# DASH_BOARD.net
KiCad netlist of a schematic drawn in EAGLE
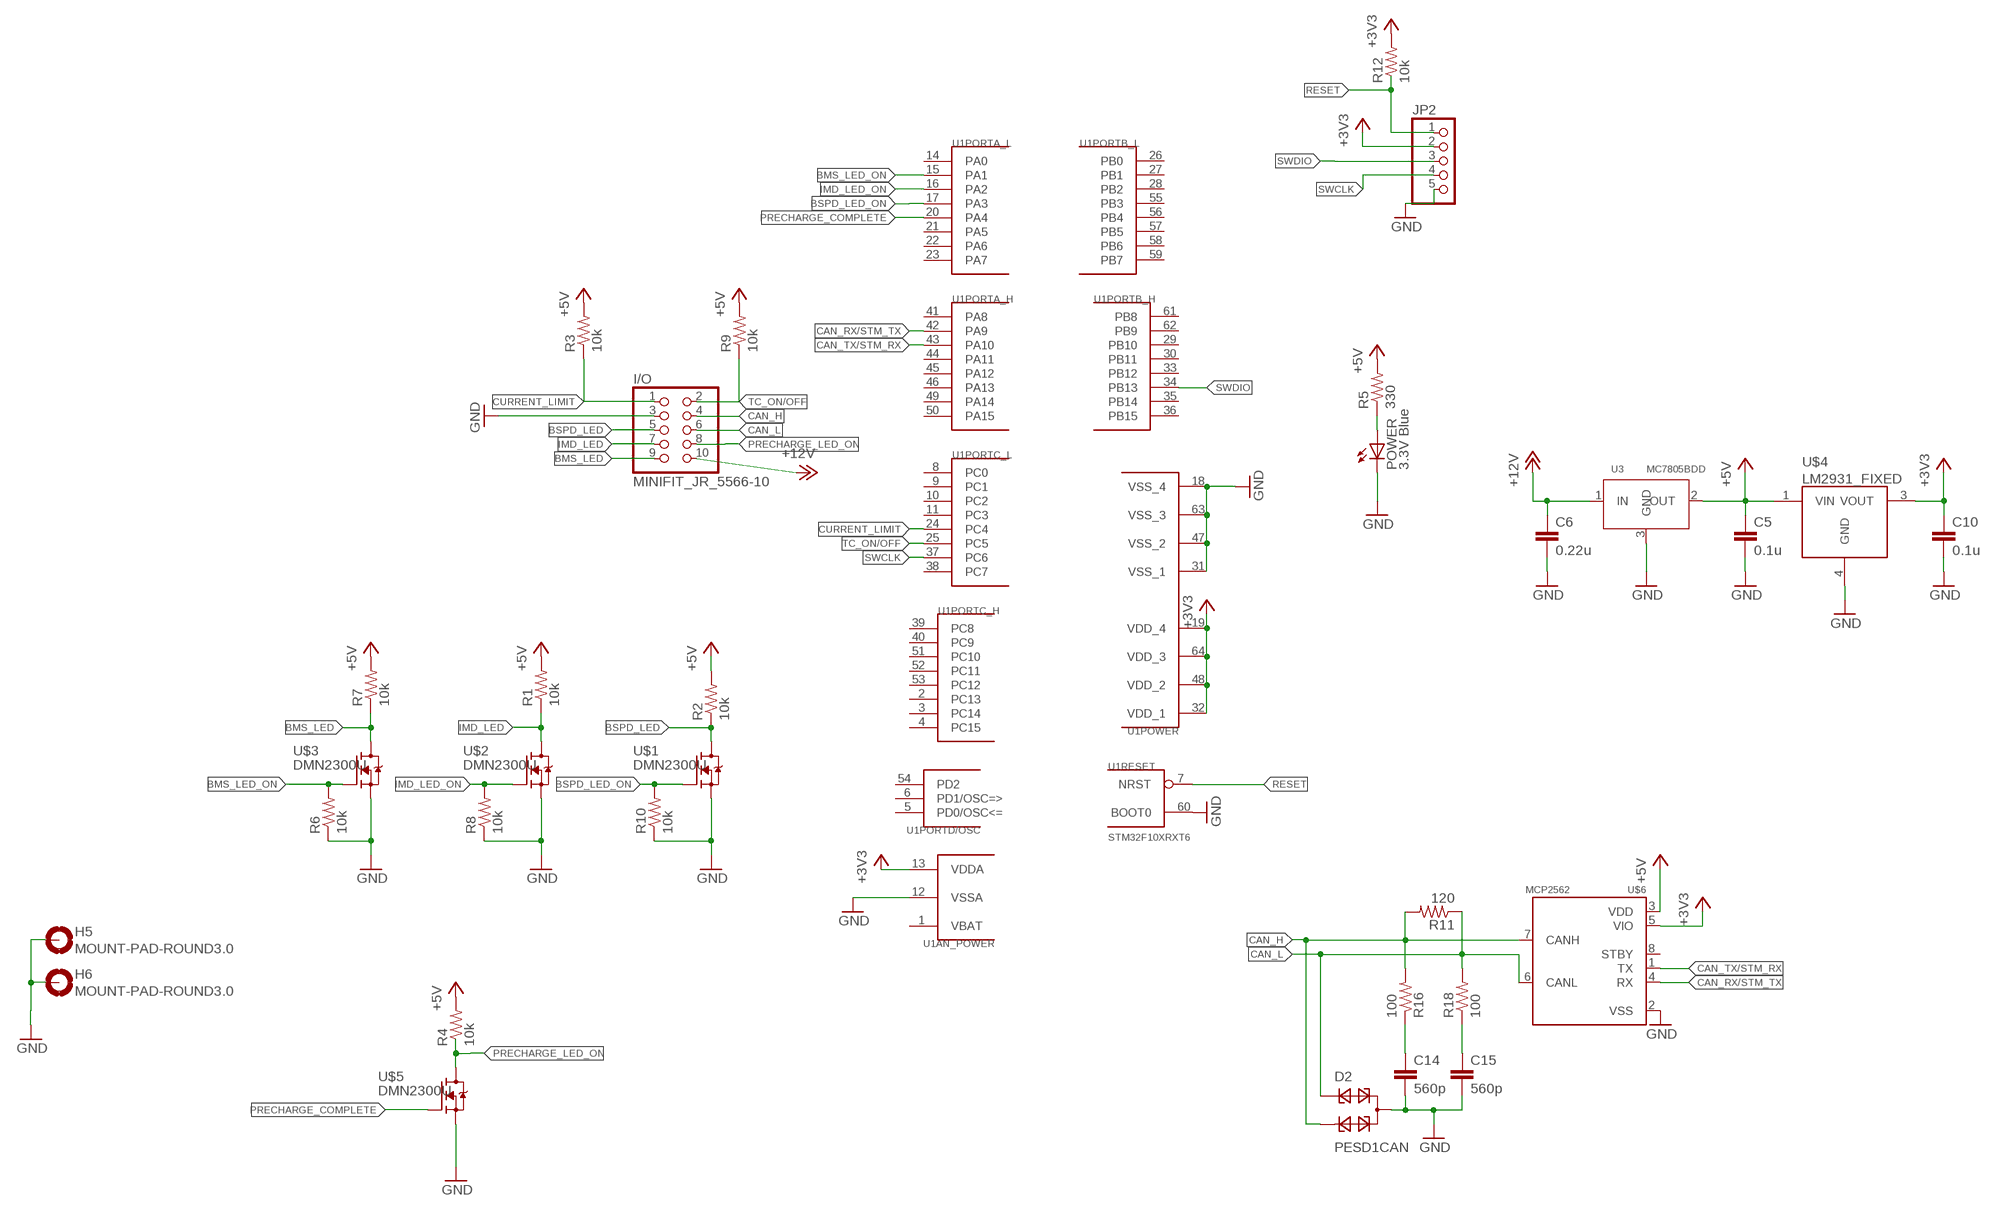
[diagram p0: schematic, sheet 1]

(export (version "E")
  (design (tool "Eeschema 10.0.6"))
  (components
    (comp (ref "C5")
      (value "0.1u")
      (footprint "eagle-import:C0805K")
      (libsource (lib "eagle-import") (part "C-EUC0805K"))
    )
    (comp (ref "C6")
      (value "0.22u")
      (footprint "eagle-import:C0805K")
      (libsource (lib "eagle-import") (part "C-EUC0805K"))
    )
    (comp (ref "C10")
      (value "0.1u")
      (footprint "eagle-import:C0805K")
      (libsource (lib "eagle-import") (part "C-EUC0805K"))
    )
    (comp (ref "C14")
      (value "560p")
      (footprint "eagle-import:C0805K")
      (libsource (lib "eagle-import") (part "C-EUC0805K"))
    )
    (comp (ref "C15")
      (value "560p")
      (footprint "eagle-import:C0805K")
      (libsource (lib "eagle-import") (part "C-EUC0805K"))
    )
    (comp (ref "D2")
      (value "PESD1CAN")
      (footprint "eagle-import:SOT23")
      (libsource (lib "eagle-import") (part "PESD1CAN"))
    )
    (comp (ref "H5")
      (value "MOUNT-PAD-ROUND3.0")
      (footprint "eagle-import:3,0-PAD")
      (libsource (lib "eagle-import") (part "MOUNT-PAD-ROUND3.0"))
    )
    (comp (ref "H6")
      (value "MOUNT-PAD-ROUND3.0")
      (footprint "eagle-import:3,0-PAD")
      (libsource (lib "eagle-import") (part "MOUNT-PAD-ROUND3.0"))
    )
    (comp (ref "I/O")
      (value "MINIFIT_JR_5566-10")
      (footprint "eagle-import:MINIFIT_JR_5566-10")
      (libsource (lib "eagle-import") (part "MINIFIT_JR_5566-10"))
    )
    (comp (ref "JP2")
      (value "PINHD-1X5")
      (footprint "eagle-import:1X05")
      (libsource (lib "eagle-import") (part "PINHD-1X5"))
    )
    (comp (ref "POWER")
      (value "3.3V Blue")
      (footprint "eagle-import:SML0805")
      (libsource (lib "eagle-import") (part "LEDSML0805"))
    )
    (comp (ref "R1")
      (value "10k")
      (footprint "eagle-import:R0805")
      (libsource (lib "eagle-import") (part "resistor_348_R-US_R0805"))
    )
    (comp (ref "R2")
      (value "10k")
      (footprint "eagle-import:R0805")
      (libsource (lib "eagle-import") (part "resistor_348_R-US_R0805"))
    )
    (comp (ref "R3")
      (value "10k")
      (footprint "eagle-import:R0805")
      (libsource (lib "eagle-import") (part "resistor_348_R-US_R0805"))
    )
    (comp (ref "R4")
      (value "10k")
      (footprint "eagle-import:R0805")
      (libsource (lib "eagle-import") (part "resistor_348_R-US_R0805"))
    )
    (comp (ref "R5")
      (value "330")
      (footprint "eagle-import:R0805")
      (libsource (lib "eagle-import") (part "R-US_R0805"))
    )
    (comp (ref "R6")
      (value "10k")
      (footprint "eagle-import:R0805")
      (libsource (lib "eagle-import") (part "resistor_348_R-US_R0805"))
    )
    (comp (ref "R7")
      (value "10k")
      (footprint "eagle-import:R0805")
      (libsource (lib "eagle-import") (part "resistor_348_R-US_R0805"))
    )
    (comp (ref "R8")
      (value "10k")
      (footprint "eagle-import:R0805")
      (libsource (lib "eagle-import") (part "resistor_348_R-US_R0805"))
    )
    (comp (ref "R9")
      (value "10k")
      (footprint "eagle-import:R0805")
      (libsource (lib "eagle-import") (part "resistor_348_R-US_R0805"))
    )
    (comp (ref "R10")
      (value "10k")
      (footprint "eagle-import:R0805")
      (libsource (lib "eagle-import") (part "resistor_348_R-US_R0805"))
    )
    (comp (ref "R11")
      (value "120")
      (footprint "eagle-import:R0805")
      (libsource (lib "eagle-import") (part "R-US_R0805"))
    )
    (comp (ref "R12")
      (value "10k")
      (footprint "eagle-import:R0805")
      (libsource (lib "eagle-import") (part "resistor_348_R-US_R0805"))
    )
    (comp (ref "R16")
      (value "100")
      (footprint "eagle-import:R0805")
      (libsource (lib "eagle-import") (part "R-US_R0805"))
    )
    (comp (ref "R18")
      (value "100")
      (footprint "eagle-import:R0805")
      (libsource (lib "eagle-import") (part "R-US_R0805"))
    )
    (comp (ref "U$1")
      (value "DMN2300U")
      (footprint "eagle-import:SOT23")
      (libsource (lib "eagle-import") (part "DMN2300U"))
    )
    (comp (ref "U$2")
      (value "DMN2300U")
      (footprint "eagle-import:SOT23")
      (libsource (lib "eagle-import") (part "DMN2300U"))
    )
    (comp (ref "U$3")
      (value "DMN2300U")
      (footprint "eagle-import:SOT23")
      (libsource (lib "eagle-import") (part "DMN2300U"))
    )
    (comp (ref "U$4")
      (value "LM2931_FIXED")
      (footprint "eagle-import:DPAK")
      (libsource (lib "eagle-import") (part "LM2931_FIXED"))
    )
    (comp (ref "U$5")
      (value "DMN2300U")
      (footprint "eagle-import:SOT23")
      (libsource (lib "eagle-import") (part "DMN2300U"))
    )
    (comp (ref "U$6")
      (value "MCP2562")
      (footprint "eagle-import:SOIC8")
      (libsource (lib "eagle-import") (part "MCP2562"))
    )
    (comp (ref "U1")
      (value "STM32F10XRXT6")
      (footprint "eagle-import:TQFP64")
      (libsource (lib "eagle-import") (part "STM32F10XRXT6"))
    )
    (comp (ref "U3")
      (value "MC7805BDD")
      (footprint "eagle-import:DPAK")
      (libsource (lib "eagle-import") (part "MC7805BDD"))
    )
  )
  (nets
    (net (code "1") (name "+3V3") (class "Default")
      (node (ref "C10") (pin "1") (pinfunction "1_1") (pintype "passive"))
      (node (ref "JP2") (pin "2") (pinfunction "2_2") (pintype "passive"))
      (node (ref "R12") (pin "2") (pinfunction "2_2") (pintype "passive"))
      (node (ref "U$4") (pin "3") (pinfunction "VOUT_3") (pintype "bidirectional"))
      (node (ref "U$6") (pin "5") (pinfunction "VIO_5") (pintype "bidirectional"))
      (node (ref "U1") (pin "13") (pinfunction "VDDA_13") (pintype "power_in"))
      (node (ref "U1") (pin "19") (pinfunction "VDD_4_19") (pintype "power_in"))
      (node (ref "U1") (pin "32") (pinfunction "VDD_1_32") (pintype "power_in"))
      (node (ref "U1") (pin "48") (pinfunction "VDD_2_48") (pintype "power_in"))
      (node (ref "U1") (pin "64") (pinfunction "VDD_3_64") (pintype "power_in"))
    )
    (net (code "2") (name "+5V") (class "Default")
      (node (ref "C5") (pin "1") (pinfunction "1_1") (pintype "passive"))
      (node (ref "R1") (pin "2") (pinfunction "2_2") (pintype "passive"))
      (node (ref "R2") (pin "2") (pinfunction "2_2") (pintype "passive"))
      (node (ref "R3") (pin "2") (pinfunction "2_2") (pintype "passive"))
      (node (ref "R4") (pin "2") (pinfunction "2_2") (pintype "passive"))
      (node (ref "R5") (pin "2") (pinfunction "2_2") (pintype "passive"))
      (node (ref "R7") (pin "2") (pinfunction "2_2") (pintype "passive"))
      (node (ref "R9") (pin "2") (pinfunction "2_2") (pintype "passive"))
      (node (ref "U$4") (pin "1") (pinfunction "VIN_1") (pintype "bidirectional"))
      (node (ref "U$6") (pin "3") (pinfunction "VDD_3") (pintype "bidirectional"))
      (node (ref "U3") (pin "2") (pinfunction "OUT_2") (pintype "bidirectional"))
    )
    (net (code "3") (name "+12V") (class "Default")
      (node (ref "C6") (pin "1") (pinfunction "1_1") (pintype "passive"))
      (node (ref "I/O") (pin "10") (pinfunction "10_10") (pintype "passive"))
      (node (ref "U3") (pin "1") (pinfunction "IN_1") (pintype "bidirectional"))
    )
    (net (code "4") (name "/VBAT") (class "Default")
      (node (ref "U1") (pin "1") (pinfunction "VBAT_1") (pintype "power_in"))
    )
    (net (code "5") (name "BMS_LED") (class "Default")
      (node (ref "I/O") (pin "9") (pinfunction "9_9") (pintype "passive"))
      (node (ref "R7") (pin "1") (pinfunction "1_1") (pintype "passive"))
      (node (ref "U$3") (pin "3") (pinfunction "D_3") (pintype "passive"))
    )
    (net (code "6") (name "BMS_LED_ON") (class "Default")
      (node (ref "R6") (pin "2") (pinfunction "2_2") (pintype "passive"))
      (node (ref "U$3") (pin "1") (pinfunction "G_1") (pintype "passive"))
      (node (ref "U1") (pin "15") (pinfunction "PA1_15") (pintype "bidirectional"))
    )
    (net (code "7") (name "BSPD_LED") (class "Default")
      (node (ref "I/O") (pin "5") (pinfunction "5_5") (pintype "passive"))
      (node (ref "R2") (pin "1") (pinfunction "1_1") (pintype "passive"))
      (node (ref "U$1") (pin "3") (pinfunction "D_3") (pintype "passive"))
    )
    (net (code "8") (name "BSPD_LED_ON") (class "Default")
      (node (ref "R10") (pin "2") (pinfunction "2_2") (pintype "passive"))
      (node (ref "U$1") (pin "1") (pinfunction "G_1") (pintype "passive"))
      (node (ref "U1") (pin "17") (pinfunction "PA3_17") (pintype "bidirectional"))
    )
    (net (code "9") (name "CAN_H") (class "Default")
      (node (ref "D2") (pin "2") (pinfunction "2_2") (pintype "passive"))
      (node (ref "I/O") (pin "4") (pinfunction "4_4") (pintype "passive"))
      (node (ref "R11") (pin "2") (pinfunction "2_2") (pintype "passive"))
      (node (ref "R16") (pin "2") (pinfunction "2_2") (pintype "passive"))
      (node (ref "U$6") (pin "7") (pinfunction "CANH_7") (pintype "bidirectional"))
    )
    (net (code "10") (name "CAN_L") (class "Default")
      (node (ref "D2") (pin "1") (pinfunction "1_1") (pintype "passive"))
      (node (ref "I/O") (pin "6") (pinfunction "6_6") (pintype "passive"))
      (node (ref "R11") (pin "1") (pinfunction "1_1") (pintype "passive"))
      (node (ref "R18") (pin "2") (pinfunction "2_2") (pintype "passive"))
      (node (ref "U$6") (pin "6") (pinfunction "CANL_6") (pintype "bidirectional"))
    )
    (net (code "11") (name "CAN_RX{slash}STM_TX") (class "Default")
      (node (ref "U$6") (pin "4") (pinfunction "RX_4") (pintype "bidirectional"))
      (node (ref "U1") (pin "42") (pinfunction "PA9_42") (pintype "bidirectional"))
    )
    (net (code "12") (name "CAN_TX{slash}STM_RX") (class "Default")
      (node (ref "U$6") (pin "1") (pinfunction "TX_1") (pintype "bidirectional"))
      (node (ref "U1") (pin "43") (pinfunction "PA10_43") (pintype "bidirectional"))
    )
    (net (code "13") (name "CURRENT_LIMIT") (class "Default")
      (node (ref "I/O") (pin "1") (pinfunction "1_1") (pintype "passive"))
      (node (ref "R3") (pin "1") (pinfunction "1_1") (pintype "passive"))
      (node (ref "U1") (pin "24") (pinfunction "PC4_24") (pintype "bidirectional"))
    )
    (net (code "14") (name "GND") (class "Default")
      (node (ref "C10") (pin "2") (pinfunction "2_2") (pintype "passive"))
      (node (ref "C14") (pin "2") (pinfunction "2_2") (pintype "passive"))
      (node (ref "C15") (pin "2") (pinfunction "2_2") (pintype "passive"))
      (node (ref "C5") (pin "2") (pinfunction "2_2") (pintype "passive"))
      (node (ref "C6") (pin "2") (pinfunction "2_2") (pintype "passive"))
      (node (ref "D2") (pin "3") (pinfunction "3_3") (pintype "passive"))
      (node (ref "H5") (pin "B3,0") (pinfunction "MOUNT_B3,0") (pintype "passive"))
      (node (ref "H6") (pin "B3,0") (pinfunction "MOUNT_B3,0") (pintype "passive"))
      (node (ref "I/O") (pin "3") (pinfunction "3_3") (pintype "passive"))
      (node (ref "JP2") (pin "5") (pinfunction "5_5") (pintype "passive"))
      (node (ref "POWER") (pin "C") (pinfunction "C_C") (pintype "passive"))
      (node (ref "R10") (pin "1") (pinfunction "1_1") (pintype "passive"))
      (node (ref "R6") (pin "1") (pinfunction "1_1") (pintype "passive"))
      (node (ref "R8") (pin "1") (pinfunction "1_1") (pintype "passive"))
      (node (ref "U$1") (pin "2") (pinfunction "S_2") (pintype "passive"))
      (node (ref "U$2") (pin "2") (pinfunction "S_2") (pintype "passive"))
      (node (ref "U$3") (pin "2") (pinfunction "S_2") (pintype "passive"))
      (node (ref "U$4") (pin "4") (pinfunction "GND_4") (pintype "bidirectional"))
      (node (ref "U$5") (pin "2") (pinfunction "S_2") (pintype "passive"))
      (node (ref "U$6") (pin "2") (pinfunction "VSS_2") (pintype "bidirectional"))
      (node (ref "U1") (pin "12") (pinfunction "VSSA_12") (pintype "power_in"))
      (node (ref "U1") (pin "18") (pinfunction "VSS_4_18") (pintype "power_in"))
      (node (ref "U1") (pin "31") (pinfunction "VSS_1_31") (pintype "power_in"))
      (node (ref "U1") (pin "47") (pinfunction "VSS_2_47") (pintype "power_in"))
      (node (ref "U1") (pin "60") (pinfunction "BOOT0_60") (pintype "input"))
      (node (ref "U1") (pin "63") (pinfunction "VSS_3_63") (pintype "power_in"))
      (node (ref "U3") (pin "3") (pinfunction "GND_3") (pintype "bidirectional"))
    )
    (net (code "15") (name "IMD_LED") (class "Default")
      (node (ref "I/O") (pin "7") (pinfunction "7_7") (pintype "passive"))
      (node (ref "R1") (pin "1") (pinfunction "1_1") (pintype "passive"))
      (node (ref "U$2") (pin "3") (pinfunction "D_3") (pintype "passive"))
    )
    (net (code "16") (name "IMD_LED_ON") (class "Default")
      (node (ref "R8") (pin "2") (pinfunction "2_2") (pintype "passive"))
      (node (ref "U$2") (pin "1") (pinfunction "G_1") (pintype "passive"))
      (node (ref "U1") (pin "16") (pinfunction "PA2_16") (pintype "bidirectional"))
    )
    (net (code "17") (name "Net-(C14-Pad1)") (class "Default")
      (node (ref "C14") (pin "1") (pinfunction "1_1") (pintype "passive"))
      (node (ref "R16") (pin "1") (pinfunction "1_1") (pintype "passive"))
    )
    (net (code "18") (name "Net-(C15-Pad1)") (class "Default")
      (node (ref "C15") (pin "1") (pinfunction "1_1") (pintype "passive"))
      (node (ref "R18") (pin "1") (pinfunction "1_1") (pintype "passive"))
    )
    (net (code "19") (name "Net-(POWER-PadA)") (class "Default")
      (node (ref "POWER") (pin "A") (pinfunction "A_A") (pintype "passive"))
      (node (ref "R5") (pin "1") (pinfunction "1_1") (pintype "passive"))
    )
    (net (code "20") (name "PRECHARGE_COMPLETE") (class "Default")
      (node (ref "U$5") (pin "1") (pinfunction "G_1") (pintype "passive"))
      (node (ref "U1") (pin "20") (pinfunction "PA4_20") (pintype "bidirectional"))
    )
    (net (code "21") (name "PRECHARGE_LED_ON") (class "Default")
      (node (ref "I/O") (pin "8") (pinfunction "8_8") (pintype "passive"))
      (node (ref "R4") (pin "1") (pinfunction "1_1") (pintype "passive"))
      (node (ref "U$5") (pin "3") (pinfunction "D_3") (pintype "passive"))
    )
    (net (code "22") (name "RESET") (class "Default")
      (node (ref "JP2") (pin "1") (pinfunction "1_1") (pintype "passive"))
      (node (ref "R12") (pin "1") (pinfunction "1_1") (pintype "passive"))
      (node (ref "U1") (pin "7") (pinfunction "NRST_7") (pintype "input"))
    )
    (net (code "23") (name "SWCLK") (class "Default")
      (node (ref "JP2") (pin "4") (pinfunction "4_4") (pintype "passive"))
      (node (ref "U1") (pin "37") (pinfunction "PC6_37") (pintype "bidirectional"))
    )
    (net (code "24") (name "SWDIO") (class "Default")
      (node (ref "JP2") (pin "3") (pinfunction "3_3") (pintype "passive"))
      (node (ref "U1") (pin "34") (pinfunction "PB13_34") (pintype "bidirectional"))
    )
    (net (code "25") (name "TC_ON{slash}OFF") (class "Default")
      (node (ref "I/O") (pin "2") (pinfunction "2_2") (pintype "passive"))
      (node (ref "R9") (pin "1") (pinfunction "1_1") (pintype "passive"))
      (node (ref "U1") (pin "25") (pinfunction "PC5_25") (pintype "bidirectional"))
    )
    (net (code "26") (name "unconnected-(U$6-STBY-Pad8)") (class "Default")
      (node (ref "U$6") (pin "8") (pinfunction "STBY_8") (pintype "bidirectional"))
    )
    (net (code "27") (name "unconnected-(U1B-PA8-Pad41)") (class "Default")
      (node (ref "U1") (pin "41") (pinfunction "PA8_41") (pintype "bidirectional"))
    )
    (net (code "28") (name "unconnected-(U1B-PA11-Pad44)") (class "Default")
      (node (ref "U1") (pin "44") (pinfunction "PA11_44") (pintype "bidirectional"))
    )
    (net (code "29") (name "unconnected-(U1B-PA12-Pad45)") (class "Default")
      (node (ref "U1") (pin "45") (pinfunction "PA12_45") (pintype "bidirectional"))
    )
    (net (code "30") (name "unconnected-(U1B-PA13-Pad46)") (class "Default")
      (node (ref "U1") (pin "46") (pinfunction "PA13_46") (pintype "bidirectional"))
    )
    (net (code "31") (name "unconnected-(U1B-PA14-Pad49)") (class "Default")
      (node (ref "U1") (pin "49") (pinfunction "PA14_49") (pintype "bidirectional"))
    )
    (net (code "32") (name "unconnected-(U1B-PA15-Pad50)") (class "Default")
      (node (ref "U1") (pin "50") (pinfunction "PA15_50") (pintype "bidirectional"))
    )
    (net (code "33") (name "unconnected-(U1C-PA0-Pad14)") (class "Default")
      (node (ref "U1") (pin "14") (pinfunction "PA0_14") (pintype "bidirectional"))
    )
    (net (code "34") (name "unconnected-(U1C-PA5-Pad21)") (class "Default")
      (node (ref "U1") (pin "21") (pinfunction "PA5_21") (pintype "bidirectional"))
    )
    (net (code "35") (name "unconnected-(U1C-PA6-Pad22)") (class "Default")
      (node (ref "U1") (pin "22") (pinfunction "PA6_22") (pintype "bidirectional"))
    )
    (net (code "36") (name "unconnected-(U1C-PA7-Pad23)") (class "Default")
      (node (ref "U1") (pin "23") (pinfunction "PA7_23") (pintype "bidirectional"))
    )
    (net (code "37") (name "unconnected-(U1D-PB8-Pad61)") (class "Default")
      (node (ref "U1") (pin "61") (pinfunction "PB8_61") (pintype "bidirectional"))
    )
    (net (code "38") (name "unconnected-(U1D-PB9-Pad62)") (class "Default")
      (node (ref "U1") (pin "62") (pinfunction "PB9_62") (pintype "bidirectional"))
    )
    (net (code "39") (name "unconnected-(U1D-PB10-Pad29)") (class "Default")
      (node (ref "U1") (pin "29") (pinfunction "PB10_29") (pintype "bidirectional"))
    )
    (net (code "40") (name "unconnected-(U1D-PB11-Pad30)") (class "Default")
      (node (ref "U1") (pin "30") (pinfunction "PB11_30") (pintype "bidirectional"))
    )
    (net (code "41") (name "unconnected-(U1D-PB12-Pad33)") (class "Default")
      (node (ref "U1") (pin "33") (pinfunction "PB12_33") (pintype "bidirectional"))
    )
    (net (code "42") (name "unconnected-(U1D-PB14-Pad35)") (class "Default")
      (node (ref "U1") (pin "35") (pinfunction "PB14_35") (pintype "bidirectional"))
    )
    (net (code "43") (name "unconnected-(U1D-PB15-Pad36)") (class "Default")
      (node (ref "U1") (pin "36") (pinfunction "PB15_36") (pintype "bidirectional"))
    )
    (net (code "44") (name "unconnected-(U1E-PB0-Pad26)") (class "Default")
      (node (ref "U1") (pin "26") (pinfunction "PB0_26") (pintype "bidirectional"))
    )
    (net (code "45") (name "unconnected-(U1E-PB1-Pad27)") (class "Default")
      (node (ref "U1") (pin "27") (pinfunction "PB1_27") (pintype "bidirectional"))
    )
    (net (code "46") (name "unconnected-(U1E-PB2-Pad28)") (class "Default")
      (node (ref "U1") (pin "28") (pinfunction "PB2_28") (pintype "bidirectional"))
    )
    (net (code "47") (name "unconnected-(U1E-PB3-Pad55)") (class "Default")
      (node (ref "U1") (pin "55") (pinfunction "PB3_55") (pintype "bidirectional"))
    )
    (net (code "48") (name "unconnected-(U1E-PB4-Pad56)") (class "Default")
      (node (ref "U1") (pin "56") (pinfunction "PB4_56") (pintype "bidirectional"))
    )
    (net (code "49") (name "unconnected-(U1E-PB5-Pad57)") (class "Default")
      (node (ref "U1") (pin "57") (pinfunction "PB5_57") (pintype "bidirectional"))
    )
    (net (code "50") (name "unconnected-(U1E-PB6-Pad58)") (class "Default")
      (node (ref "U1") (pin "58") (pinfunction "PB6_58") (pintype "bidirectional"))
    )
    (net (code "51") (name "unconnected-(U1E-PB7-Pad59)") (class "Default")
      (node (ref "U1") (pin "59") (pinfunction "PB7_59") (pintype "bidirectional"))
    )
    (net (code "52") (name "unconnected-(U1F-PC8-Pad39)") (class "Default")
      (node (ref "U1") (pin "39") (pinfunction "PC8_39") (pintype "bidirectional"))
    )
    (net (code "53") (name "unconnected-(U1F-PC9-Pad40)") (class "Default")
      (node (ref "U1") (pin "40") (pinfunction "PC9_40") (pintype "bidirectional"))
    )
    (net (code "54") (name "unconnected-(U1F-PC10-Pad51)") (class "Default")
      (node (ref "U1") (pin "51") (pinfunction "PC10_51") (pintype "bidirectional"))
    )
    (net (code "55") (name "unconnected-(U1F-PC11-Pad52)") (class "Default")
      (node (ref "U1") (pin "52") (pinfunction "PC11_52") (pintype "bidirectional"))
    )
    (net (code "56") (name "unconnected-(U1F-PC12-Pad53)") (class "Default")
      (node (ref "U1") (pin "53") (pinfunction "PC12_53") (pintype "bidirectional"))
    )
    (net (code "57") (name "unconnected-(U1F-PC13-Pad2)") (class "Default")
      (node (ref "U1") (pin "2") (pinfunction "PC13_2") (pintype "bidirectional"))
    )
    (net (code "58") (name "unconnected-(U1F-PC14-Pad3)") (class "Default")
      (node (ref "U1") (pin "3") (pinfunction "PC14_3") (pintype "bidirectional"))
    )
    (net (code "59") (name "unconnected-(U1F-PC15-Pad4)") (class "Default")
      (node (ref "U1") (pin "4") (pinfunction "PC15_4") (pintype "bidirectional"))
    )
    (net (code "60") (name "unconnected-(U1G-PC0-Pad8)") (class "Default")
      (node (ref "U1") (pin "8") (pinfunction "PC0_8") (pintype "bidirectional"))
    )
    (net (code "61") (name "unconnected-(U1G-PC1-Pad9)") (class "Default")
      (node (ref "U1") (pin "9") (pinfunction "PC1_9") (pintype "bidirectional"))
    )
    (net (code "62") (name "unconnected-(U1G-PC2-Pad10)") (class "Default")
      (node (ref "U1") (pin "10") (pinfunction "PC2_10") (pintype "bidirectional"))
    )
    (net (code "63") (name "unconnected-(U1G-PC3-Pad11)") (class "Default")
      (node (ref "U1") (pin "11") (pinfunction "PC3_11") (pintype "bidirectional"))
    )
    (net (code "64") (name "unconnected-(U1G-PC7-Pad38)") (class "Default")
      (node (ref "U1") (pin "38") (pinfunction "PC7_38") (pintype "bidirectional"))
    )
    (net (code "65") (name "unconnected-(U1H-PD0{slash}OSC<=-Pad5)") (class "Default")
      (node (ref "U1") (pin "5") (pinfunction "PD0/OSC<=_5") (pintype "bidirectional"))
    )
    (net (code "66") (name "unconnected-(U1H-PD1{slash}OSC=>-Pad6)") (class "Default")
      (node (ref "U1") (pin "6") (pinfunction "PD1/OSC=>_6") (pintype "bidirectional"))
    )
    (net (code "67") (name "unconnected-(U1H-PD2-Pad54)") (class "Default")
      (node (ref "U1") (pin "54") (pinfunction "PD2_54") (pintype "bidirectional"))
    )
  )
)
